# design.net
KiCad netlist of a schematic drawn in Altium Designer
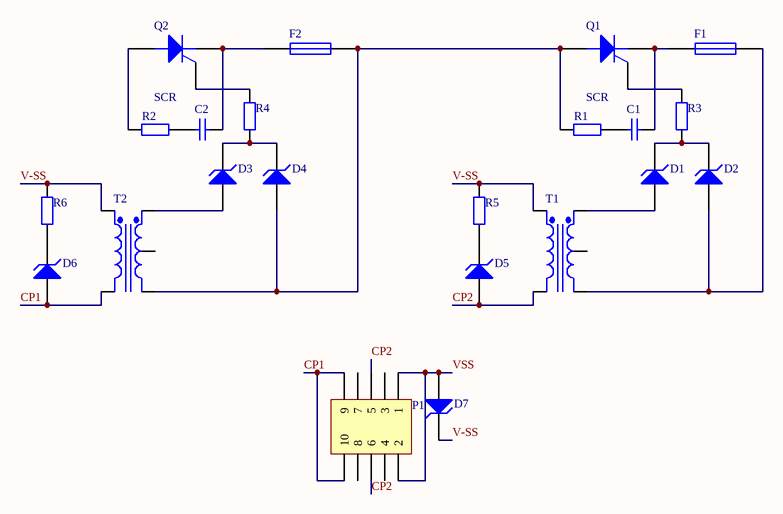
[diagram p0: 集成晶闸管.SchDoc]

(export (version "E")
  (design (tool "Eeschema 10.0.6"))
  (components
    (comp (ref "C1")
      (value "Cap")
      (footprint "RAD-0.3")
      (description "Capacitor")
      (fields (field (name "PUBLISHER") "Altium Limited"))
      (libsource (lib "Miscellaneous Devices") (part "Cap"))
    )
    (comp (ref "C2")
      (value "Cap")
      (footprint "RAD-0.3")
      (description "Capacitor")
      (fields (field (name "PUBLISHER") "Altium Limited"))
      (libsource (lib "Miscellaneous Devices") (part "Cap"))
    )
    (comp (ref "D1")
      (value "D Zener")
      (footprint "DIODE-0.7")
      (description "Zener Diode")
      (fields (field (name "PUBLISHER") "Altium Limited"))
      (libsource (lib "Miscellaneous Devices") (part "D Zener"))
    )
    (comp (ref "D2")
      (value "D Zener")
      (footprint "DIODE-0.7")
      (description "Zener Diode")
      (fields (field (name "PUBLISHER") "Altium Limited"))
      (libsource (lib "Miscellaneous Devices") (part "D Zener"))
    )
    (comp (ref "D3")
      (value "D Zener")
      (footprint "DIODE-0.7")
      (description "Zener Diode")
      (fields (field (name "PUBLISHER") "Altium Limited"))
      (libsource (lib "Miscellaneous Devices") (part "D Zener"))
    )
    (comp (ref "D4")
      (value "D Zener")
      (footprint "DIODE-0.7")
      (description "Zener Diode")
      (fields (field (name "PUBLISHER") "Altium Limited"))
      (libsource (lib "Miscellaneous Devices") (part "D Zener"))
    )
    (comp (ref "D5")
      (value "D Zener")
      (footprint "DIODE-0.7")
      (description "Zener Diode")
      (fields (field (name "PUBLISHER") "Altium Limited"))
      (libsource (lib "Miscellaneous Devices") (part "D Zener"))
    )
    (comp (ref "D6")
      (value "D Zener")
      (footprint "DIODE-0.7")
      (description "Zener Diode")
      (fields (field (name "PUBLISHER") "Altium Limited"))
      (libsource (lib "Miscellaneous Devices") (part "D Zener"))
    )
    (comp (ref "D7")
      (value "D Zener")
      (footprint "DIODE-0.7")
      (description "Zener Diode")
      (fields (field (name "PUBLISHER") "Altium Limited"))
      (libsource (lib "Miscellaneous Devices") (part "D Zener"))
    )
    (comp (ref "F1")
      (value "Fuse 1")
      (footprint "PIN-W2/E2.8")
      (description "Fuse")
      (fields (field (name "PUBLISHER") "Altium Limited"))
      (libsource (lib "Miscellaneous Devices") (part "Fuse 1"))
    )
    (comp (ref "F2")
      (value "Fuse 1")
      (footprint "PIN-W2/E2.8")
      (description "Fuse")
      (fields (field (name "PUBLISHER") "Altium Limited"))
      (libsource (lib "Miscellaneous Devices") (part "Fuse 1"))
    )
    (comp (ref "P1")
      (value "Header 5X2")
      (footprint "HDR2X5")
      (description "Header, 5-Pin, Dual row")
      (fields (field (name "PUBLISHER") "Altium Limited"))
      (libsource (lib "Miscellaneous Connectors") (part "Header 5X2"))
    )
    (comp (ref "Q1")
      (value "SCR")
      (footprint "TO-220-AB")
      (description "Silicon Controlled Rectifier")
      (fields (field (name "PUBLISHER") "Altium Limited"))
      (libsource (lib "Miscellaneous Devices") (part "SCR"))
    )
    (comp (ref "Q2")
      (value "SCR")
      (footprint "TO-220-AB")
      (description "Silicon Controlled Rectifier")
      (fields (field (name "PUBLISHER") "Altium Limited"))
      (libsource (lib "Miscellaneous Devices") (part "SCR"))
    )
    (comp (ref "R1")
      (value "Res2")
      (footprint "AXIAL-0.4")
      (description "Resistor")
      (fields (field (name "PUBLISHER") "Altium Limited"))
      (libsource (lib "Miscellaneous Devices") (part "Res2"))
    )
    (comp (ref "R2")
      (value "Res2")
      (footprint "AXIAL-0.4")
      (description "Resistor")
      (fields (field (name "PUBLISHER") "Altium Limited"))
      (libsource (lib "Miscellaneous Devices") (part "Res2"))
    )
    (comp (ref "R3")
      (value "Res2")
      (footprint "AXIAL-0.4")
      (description "Resistor")
      (fields (field (name "PUBLISHER") "Altium Limited"))
      (libsource (lib "") (part "Res2_2"))
    )
    (comp (ref "R4")
      (value "Res2")
      (footprint "AXIAL-0.4")
      (description "Resistor")
      (fields (field (name "PUBLISHER") "Altium Limited"))
      (libsource (lib "") (part "Res2_1"))
    )
    (comp (ref "R5")
      (value "Res2")
      (footprint "AXIAL-0.4")
      (description "Resistor")
      (fields (field (name "PUBLISHER") "Altium Limited"))
      (libsource (lib "") (part "Res2_1"))
    )
    (comp (ref "R6")
      (value "Res2")
      (footprint "AXIAL-0.4")
      (description "Resistor")
      (fields (field (name "PUBLISHER") "Altium Limited"))
      (libsource (lib "") (part "Res2_1"))
    )
    (comp (ref "T1")
      (value "Trans CT")
      (footprint "TRF_5")
      (description "Center-Tapped Transformer (Coupled Inductor Model)")
      (fields (field (name "PUBLISHER") "Altium Limited"))
      (libsource (lib "Miscellaneous Devices") (part "Trans CT"))
    )
    (comp (ref "T2")
      (value "Trans CT")
      (footprint "TRF_5")
      (description "Center-Tapped Transformer (Coupled Inductor Model)")
      (fields (field (name "PUBLISHER") "Altium Limited"))
      (libsource (lib "Miscellaneous Devices") (part "Trans CT"))
    )
  )
  (nets
    (net (code "1") (name "/CP1") (class "Default")
      (node (ref "D6") (pin "1") (pinfunction "A_1") (pintype "passive"))
      (node (ref "P1") (pin "10") (pinfunction "10_10") (pintype "passive"))
      (node (ref "P1") (pin "9") (pinfunction "9_9") (pintype "passive"))
      (node (ref "T2") (pin "2") (pinfunction "Pri-_2") (pintype "passive"))
    )
    (net (code "2") (name "/CP2") (class "Default")
      (node (ref "D5") (pin "1") (pinfunction "A_1") (pintype "passive"))
      (node (ref "P1") (pin "5") (pinfunction "5_5") (pintype "passive"))
      (node (ref "P1") (pin "6") (pinfunction "6_6") (pintype "passive"))
      (node (ref "T1") (pin "2") (pinfunction "Pri-_2") (pintype "passive"))
    )
    (net (code "3") (name "/V-SS") (class "Default")
      (node (ref "D7") (pin "2") (pinfunction "K_2") (pintype "passive"))
      (node (ref "R5") (pin "2") (pinfunction "2_2") (pintype "passive"))
      (node (ref "R6") (pin "2") (pinfunction "2_2") (pintype "passive"))
      (node (ref "T1") (pin "1") (pinfunction "Pri+_1") (pintype "passive"))
      (node (ref "T2") (pin "1") (pinfunction "Pri+_1") (pintype "passive"))
    )
    (net (code "4") (name "/VSS") (class "Default")
      (node (ref "D7") (pin "1") (pinfunction "A_1") (pintype "passive"))
      (node (ref "P1") (pin "1") (pinfunction "1_1") (pintype "passive"))
      (node (ref "P1") (pin "2") (pinfunction "2_2") (pintype "passive"))
    )
    (net (code "5") (name "Net-(C1-Pad1)") (class "Default")
      (node (ref "C1") (pin "1") (pinfunction "1_1") (pintype "passive"))
      (node (ref "R1") (pin "2") (pinfunction "2_2") (pintype "passive"))
    )
    (net (code "6") (name "Net-(C2-Pad1)") (class "Default")
      (node (ref "C2") (pin "1") (pinfunction "1_1") (pintype "passive"))
      (node (ref "R2") (pin "2") (pinfunction "2_2") (pintype "passive"))
    )
    (net (code "7") (name "Net-(D1-A)") (class "Default")
      (node (ref "D1") (pin "1") (pinfunction "A_1") (pintype "passive"))
      (node (ref "T1") (pin "3") (pinfunction "Sec+_3") (pintype "passive"))
    )
    (net (code "8") (name "Net-(D1-K)") (class "Default")
      (node (ref "D1") (pin "2") (pinfunction "K_2") (pintype "passive"))
      (node (ref "D2") (pin "2") (pinfunction "K_2") (pintype "passive"))
      (node (ref "R3") (pin "2") (pinfunction "2_2") (pintype "passive"))
    )
    (net (code "9") (name "Net-(D2-A)") (class "Default")
      (node (ref "D2") (pin "1") (pinfunction "A_1") (pintype "passive"))
      (node (ref "F1") (pin "2") (pinfunction "2_2") (pintype "passive"))
      (node (ref "T1") (pin "5") (pinfunction "Sec-_5") (pintype "passive"))
    )
    (net (code "10") (name "Net-(D3-A)") (class "Default")
      (node (ref "D3") (pin "1") (pinfunction "A_1") (pintype "passive"))
      (node (ref "T2") (pin "3") (pinfunction "Sec+_3") (pintype "passive"))
    )
    (net (code "11") (name "Net-(D3-K)") (class "Default")
      (node (ref "D3") (pin "2") (pinfunction "K_2") (pintype "passive"))
      (node (ref "D4") (pin "2") (pinfunction "K_2") (pintype "passive"))
      (node (ref "R4") (pin "1") (pinfunction "1_1") (pintype "passive"))
    )
    (net (code "12") (name "Net-(D4-A)") (class "Default")
      (node (ref "D4") (pin "1") (pinfunction "A_1") (pintype "passive"))
      (node (ref "F2") (pin "2") (pinfunction "2_2") (pintype "passive"))
      (node (ref "Q1") (pin "1") (pinfunction "A_1") (pintype "passive"))
      (node (ref "R1") (pin "1") (pinfunction "1_1") (pintype "passive"))
      (node (ref "T2") (pin "5") (pinfunction "Sec-_5") (pintype "passive"))
    )
    (net (code "13") (name "Net-(D5-K)") (class "Default")
      (node (ref "D5") (pin "2") (pinfunction "K_2") (pintype "passive"))
      (node (ref "R5") (pin "1") (pinfunction "1_1") (pintype "passive"))
    )
    (net (code "14") (name "Net-(D6-K)") (class "Default")
      (node (ref "D6") (pin "2") (pinfunction "K_2") (pintype "passive"))
      (node (ref "R6") (pin "1") (pinfunction "1_1") (pintype "passive"))
    )
    (net (code "15") (name "Net-(Q1-G)") (class "Default")
      (node (ref "Q1") (pin "2") (pinfunction "G_2") (pintype "passive"))
      (node (ref "R3") (pin "1") (pinfunction "1_1") (pintype "passive"))
    )
    (net (code "16") (name "Net-(Q1-K)") (class "Default")
      (node (ref "C1") (pin "2") (pinfunction "2_2") (pintype "passive"))
      (node (ref "F1") (pin "1") (pinfunction "1_1") (pintype "passive"))
      (node (ref "Q1") (pin "3") (pinfunction "K_3") (pintype "passive"))
    )
    (net (code "17") (name "Net-(Q2-A)") (class "Default")
      (node (ref "Q2") (pin "1") (pinfunction "A_1") (pintype "passive"))
      (node (ref "R2") (pin "1") (pinfunction "1_1") (pintype "passive"))
    )
    (net (code "18") (name "Net-(Q2-G)") (class "Default")
      (node (ref "Q2") (pin "2") (pinfunction "G_2") (pintype "passive"))
      (node (ref "R4") (pin "2") (pinfunction "2_2") (pintype "passive"))
    )
    (net (code "19") (name "Net-(Q2-K)") (class "Default")
      (node (ref "C2") (pin "2") (pinfunction "2_2") (pintype "passive"))
      (node (ref "F2") (pin "1") (pinfunction "1_1") (pintype "passive"))
      (node (ref "Q2") (pin "3") (pinfunction "K_3") (pintype "passive"))
    )
    (net (code "20") (name "unconnected-(P1-Pad3)") (class "Default")
      (node (ref "P1") (pin "3") (pinfunction "3_3") (pintype "passive"))
    )
    (net (code "21") (name "unconnected-(P1-Pad4)") (class "Default")
      (node (ref "P1") (pin "4") (pinfunction "4_4") (pintype "passive"))
    )
    (net (code "22") (name "unconnected-(P1-Pad7)") (class "Default")
      (node (ref "P1") (pin "7") (pinfunction "7_7") (pintype "passive"))
    )
    (net (code "23") (name "unconnected-(P1-Pad8)") (class "Default")
      (node (ref "P1") (pin "8") (pinfunction "8_8") (pintype "passive"))
    )
    (net (code "24") (name "unconnected-(T1-SecCT-Pad4)") (class "Default")
      (node (ref "T1") (pin "4") (pinfunction "SecCT_4") (pintype "passive"))
    )
    (net (code "25") (name "unconnected-(T2-SecCT-Pad4)") (class "Default")
      (node (ref "T2") (pin "4") (pinfunction "SecCT_4") (pintype "passive"))
    )
  )
)
